# ATMEGA16.net
KiCad netlist of a schematic drawn in Altium Designer
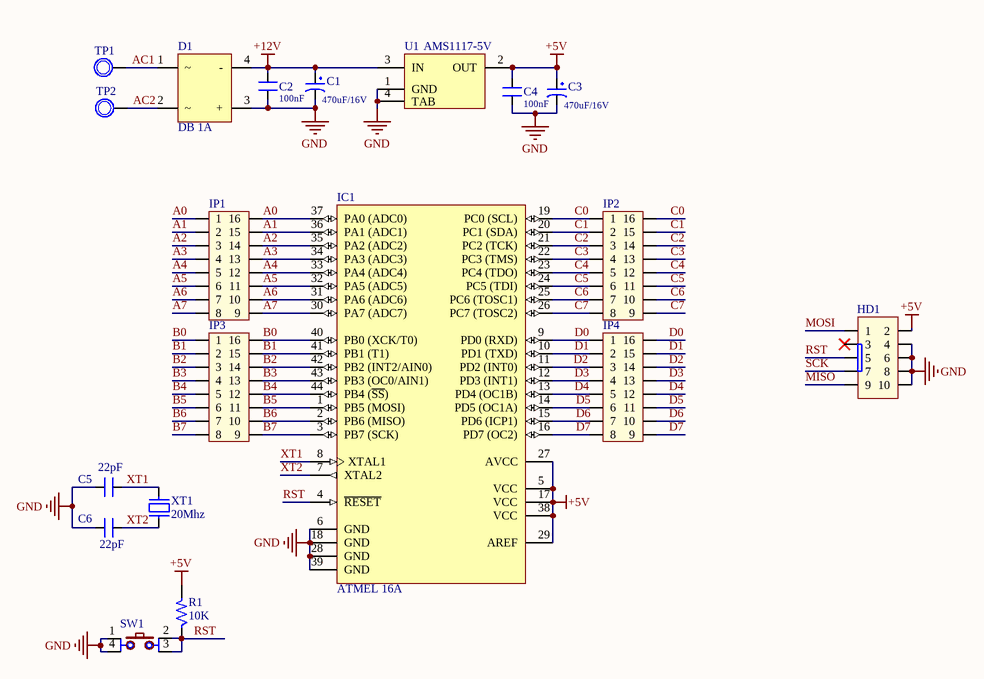
[diagram p0: ATMEGA16.SchDoc]

(export (version "E")
  (design (tool "Eeschema 10.0.6"))
  (components
    (comp (ref "C1")
      (value "470uF/16V")
      (footprint "C-TANT-7343")
      (libsource (lib "MrQuan") (part "Capacitor"))
    )
    (comp (ref "C2") (value "100nF") (footprint "CER-0805") (libsource (lib "MrQuan") (part "Ceramic")))
    (comp (ref "C3")
      (value "470uF/16V")
      (footprint "C-TANT-7343")
      (libsource (lib "MrQuan") (part "Capacitor"))
    )
    (comp (ref "C4") (value "100nF") (footprint "CER-0805") (libsource (lib "MrQuan") (part "Ceramic")))
    (comp (ref "C5") (value "22pF") (footprint "CER-0805") (libsource (lib "MrQuan") (part "Ceramic")))
    (comp (ref "C6") (value "22pF") (footprint "CER-0805") (libsource (lib "MrQuan") (part "Ceramic")))
    (comp (ref "D1")
      (value "DB 1A")
      (footprint "D-DB-1A-SMD")
      (libsource (lib "doAnTotNghiep2017Lib") (part "DB"))
    )
    (comp (ref "HD1") (value "Header 5x2") (footprint "Hed2X5") (libsource (lib "PART") (part "HED5x2_S")))
    (comp (ref "IC1")
      (value "ATMEL 16A")
      (footprint "TQFP44")
      (libsource (lib "LIBRARY") (part "ATmega16A-AU"))
    )
    (comp (ref "IP1") (value "JP8X2") (footprint "JP8X2") (libsource (lib "syhaunguyen") (part "JP8X2")))
    (comp (ref "IP2") (value "JP8X2") (footprint "JP8X2") (libsource (lib "syhaunguyen") (part "JP8X2")))
    (comp (ref "IP3") (value "JP8X2") (footprint "JP8X2") (libsource (lib "syhaunguyen") (part "JP8X2")))
    (comp (ref "IP4") (value "JP8X2") (footprint "JP8X2") (libsource (lib "syhaunguyen") (part "JP8X2")))
    (comp (ref "R1") (value "10K") (footprint "RES-0805") (libsource (lib "MrQuan") (part "Res1/4W")))
    (comp (ref "SW1")
      (value "SW")
      (footprint "SW2-SMD")
      (description "Switch button 4 pin")
      (libsource (lib "LIBRARY") (part "SW4"))
    )
    (comp (ref "TP1") (value "TP") (footprint "MrQuan:TP") (libsource (lib "MrQuan") (part "TP")))
    (comp (ref "TP2") (value "TP") (footprint "MrQuan:TP") (libsource (lib "MrQuan") (part "TP")))
    (comp (ref "U1")
      (value "AMS1117-5V")
      (footprint "LM1117")
      (description "800mA Low-Dropout Linear Regulator")
      (fields
        (field (name "PARTNUMBER") "LM1117IMP-3.3")
        (field (name "MANUFACTURER") "National Semiconductor")
        (field (name "PUBLISHER") "Altium Limited")
      )
      (libsource (lib "VNSKILLS2014-ASM") (part "LM1117IMP-3.3"))
    )
    (comp (ref "XT1")
      (value "20Mhz")
      (footprint "XTAL-RU49/4")
      (description "Crystal, 32.768 KHz, -40 to 85 degC, 3.2 x 1.5 x 0.9 mm SMD")
      (libsource (lib "LIBRARY") (part "XT2"))
    )
  )
  (nets
    (net (code "1") (name "+5V") (class "Default")
      (node (ref "C3") (pin "1") (pinfunction "1_1") (pintype "passive"))
      (node (ref "C4") (pin "2") (pinfunction "2_2") (pintype "passive"))
      (node (ref "HD1") (pin "2") (pinfunction "2_2") (pintype "passive"))
      (node (ref "IC1") (pin "17") (pinfunction "VCC_17") (pintype "power_in"))
      (node (ref "IC1") (pin "27") (pinfunction "AVCC_27") (pintype "power_in"))
      (node (ref "IC1") (pin "29") (pinfunction "AREF_29") (pintype "power_in"))
      (node (ref "IC1") (pin "38") (pinfunction "VCC_38") (pintype "power_in"))
      (node (ref "IC1") (pin "5") (pinfunction "VCC_5") (pintype "power_in"))
      (node (ref "R1") (pin "2") (pinfunction "2_2") (pintype "passive"))
      (node (ref "U1") (pin "2") (pinfunction "OUT_2") (pintype "power_in"))
    )
    (net (code "2") (name "+12V") (class "Default")
      (node (ref "C1") (pin "1") (pinfunction "1_1") (pintype "passive"))
      (node (ref "C2") (pin "2") (pinfunction "2_2") (pintype "passive"))
      (node (ref "D1") (pin "4") (pinfunction "-_4") (pintype "passive"))
      (node (ref "U1") (pin "3") (pinfunction "IN_3") (pintype "power_in"))
    )
    (net (code "3") (name "/A0") (class "Default")
      (node (ref "IC1") (pin "37") (pinfunction "PA0_(ADC0)_37") (pintype "bidirectional"))
      (node (ref "IP1") (pin "1") (pinfunction "1_1") (pintype "passive"))
      (node (ref "IP1") (pin "16") (pinfunction "16_16") (pintype "passive"))
    )
    (net (code "4") (name "/A1") (class "Default")
      (node (ref "IC1") (pin "36") (pinfunction "PA1_(ADC1)_36") (pintype "bidirectional"))
      (node (ref "IP1") (pin "15") (pinfunction "15_15") (pintype "passive"))
      (node (ref "IP1") (pin "2") (pinfunction "2_2") (pintype "passive"))
    )
    (net (code "5") (name "/A2") (class "Default")
      (node (ref "IC1") (pin "35") (pinfunction "PA2_(ADC2)_35") (pintype "bidirectional"))
      (node (ref "IP1") (pin "14") (pinfunction "14_14") (pintype "passive"))
      (node (ref "IP1") (pin "3") (pinfunction "3_3") (pintype "passive"))
    )
    (net (code "6") (name "/A3") (class "Default")
      (node (ref "IC1") (pin "34") (pinfunction "PA3_(ADC3)_34") (pintype "bidirectional"))
      (node (ref "IP1") (pin "13") (pinfunction "13_13") (pintype "passive"))
      (node (ref "IP1") (pin "4") (pinfunction "4_4") (pintype "passive"))
    )
    (net (code "7") (name "/A4") (class "Default")
      (node (ref "IC1") (pin "33") (pinfunction "PA4_(ADC4)_33") (pintype "bidirectional"))
      (node (ref "IP1") (pin "12") (pinfunction "12_12") (pintype "passive"))
      (node (ref "IP1") (pin "5") (pinfunction "5_5") (pintype "passive"))
    )
    (net (code "8") (name "/A5") (class "Default")
      (node (ref "IC1") (pin "32") (pinfunction "PA5_(ADC5)_32") (pintype "bidirectional"))
      (node (ref "IP1") (pin "11") (pinfunction "11_11") (pintype "passive"))
      (node (ref "IP1") (pin "6") (pinfunction "6_6") (pintype "passive"))
    )
    (net (code "9") (name "/A6") (class "Default")
      (node (ref "IC1") (pin "31") (pinfunction "PA6_(ADC6)_31") (pintype "bidirectional"))
      (node (ref "IP1") (pin "10") (pinfunction "10_10") (pintype "passive"))
      (node (ref "IP1") (pin "7") (pinfunction "7_7") (pintype "passive"))
    )
    (net (code "10") (name "/A7") (class "Default")
      (node (ref "IC1") (pin "30") (pinfunction "PA7_(ADC7)_30") (pintype "bidirectional"))
      (node (ref "IP1") (pin "8") (pinfunction "8_8") (pintype "passive"))
      (node (ref "IP1") (pin "9") (pinfunction "9_9") (pintype "passive"))
    )
    (net (code "11") (name "/AC1") (class "Default")
      (node (ref "D1") (pin "1") (pinfunction "~_1") (pintype "passive"))
      (node (ref "TP1") (pin "1") (pintype "passive"))
    )
    (net (code "12") (name "/AC2") (class "Default")
      (node (ref "D1") (pin "2") (pinfunction "~_2") (pintype "passive"))
      (node (ref "TP2") (pin "1") (pintype "passive"))
    )
    (net (code "13") (name "/B0") (class "Default")
      (node (ref "IC1") (pin "40") (pinfunction "PB0_(XCK/T0)_40") (pintype "bidirectional"))
      (node (ref "IP3") (pin "1") (pinfunction "1_1") (pintype "passive"))
      (node (ref "IP3") (pin "16") (pinfunction "16_16") (pintype "passive"))
    )
    (net (code "14") (name "/B1") (class "Default")
      (node (ref "IC1") (pin "41") (pinfunction "PB1_(T1)_41") (pintype "bidirectional"))
      (node (ref "IP3") (pin "15") (pinfunction "15_15") (pintype "passive"))
      (node (ref "IP3") (pin "2") (pinfunction "2_2") (pintype "passive"))
    )
    (net (code "15") (name "/B2") (class "Default")
      (node (ref "IC1") (pin "42") (pinfunction "PB2_(INT2/AIN0)_42") (pintype "bidirectional"))
      (node (ref "IP3") (pin "14") (pinfunction "14_14") (pintype "passive"))
      (node (ref "IP3") (pin "3") (pinfunction "3_3") (pintype "passive"))
    )
    (net (code "16") (name "/B3") (class "Default")
      (node (ref "IC1") (pin "43") (pinfunction "PB3_(OC0/AIN1)_43") (pintype "bidirectional"))
      (node (ref "IP3") (pin "13") (pinfunction "13_13") (pintype "passive"))
      (node (ref "IP3") (pin "4") (pinfunction "4_4") (pintype "passive"))
    )
    (net (code "17") (name "/B4") (class "Default")
      (node (ref "IC1") (pin "44") (pinfunction "PB4_(~{SS})_44") (pintype "bidirectional"))
      (node (ref "IP3") (pin "12") (pinfunction "12_12") (pintype "passive"))
      (node (ref "IP3") (pin "5") (pinfunction "5_5") (pintype "passive"))
    )
    (net (code "18") (name "/B5") (class "Default")
      (node (ref "IC1") (pin "1") (pinfunction "PB5_(MOSI)_1") (pintype "bidirectional"))
      (node (ref "IP3") (pin "11") (pinfunction "11_11") (pintype "passive"))
      (node (ref "IP3") (pin "6") (pinfunction "6_6") (pintype "passive"))
    )
    (net (code "19") (name "/B6") (class "Default")
      (node (ref "IC1") (pin "2") (pinfunction "PB6_(MISO)_2") (pintype "bidirectional"))
      (node (ref "IP3") (pin "10") (pinfunction "10_10") (pintype "passive"))
      (node (ref "IP3") (pin "7") (pinfunction "7_7") (pintype "passive"))
    )
    (net (code "20") (name "/B7") (class "Default")
      (node (ref "IC1") (pin "3") (pinfunction "PB7_(SCK)_3") (pintype "bidirectional"))
      (node (ref "IP3") (pin "8") (pinfunction "8_8") (pintype "passive"))
      (node (ref "IP3") (pin "9") (pinfunction "9_9") (pintype "passive"))
    )
    (net (code "21") (name "/C0") (class "Default")
      (node (ref "IC1") (pin "19") (pinfunction "PC0_(SCL)_19") (pintype "bidirectional"))
      (node (ref "IP2") (pin "1") (pinfunction "1_1") (pintype "passive"))
      (node (ref "IP2") (pin "16") (pinfunction "16_16") (pintype "passive"))
    )
    (net (code "22") (name "/C1") (class "Default")
      (node (ref "IC1") (pin "20") (pinfunction "PC1_(SDA)_20") (pintype "bidirectional"))
      (node (ref "IP2") (pin "15") (pinfunction "15_15") (pintype "passive"))
      (node (ref "IP2") (pin "2") (pinfunction "2_2") (pintype "passive"))
    )
    (net (code "23") (name "/C2") (class "Default")
      (node (ref "IC1") (pin "21") (pinfunction "PC2_(TCK)_21") (pintype "bidirectional"))
      (node (ref "IP2") (pin "14") (pinfunction "14_14") (pintype "passive"))
      (node (ref "IP2") (pin "3") (pinfunction "3_3") (pintype "passive"))
    )
    (net (code "24") (name "/C3") (class "Default")
      (node (ref "IC1") (pin "22") (pinfunction "PC3_(TMS)_22") (pintype "bidirectional"))
      (node (ref "IP2") (pin "13") (pinfunction "13_13") (pintype "passive"))
      (node (ref "IP2") (pin "4") (pinfunction "4_4") (pintype "passive"))
    )
    (net (code "25") (name "/C4") (class "Default")
      (node (ref "IC1") (pin "23") (pinfunction "PC4_(TDO)_23") (pintype "bidirectional"))
      (node (ref "IP2") (pin "12") (pinfunction "12_12") (pintype "passive"))
      (node (ref "IP2") (pin "5") (pinfunction "5_5") (pintype "passive"))
    )
    (net (code "26") (name "/C5") (class "Default")
      (node (ref "IC1") (pin "24") (pinfunction "PC5_(TDI)_24") (pintype "bidirectional"))
      (node (ref "IP2") (pin "11") (pinfunction "11_11") (pintype "passive"))
      (node (ref "IP2") (pin "6") (pinfunction "6_6") (pintype "passive"))
    )
    (net (code "27") (name "/C6") (class "Default")
      (node (ref "IC1") (pin "25") (pinfunction "PC6_(TOSC1)_25") (pintype "bidirectional"))
      (node (ref "IP2") (pin "10") (pinfunction "10_10") (pintype "passive"))
      (node (ref "IP2") (pin "7") (pinfunction "7_7") (pintype "passive"))
    )
    (net (code "28") (name "/C7") (class "Default")
      (node (ref "IC1") (pin "26") (pinfunction "PC7_(TOSC2)_26") (pintype "bidirectional"))
      (node (ref "IP2") (pin "8") (pinfunction "8_8") (pintype "passive"))
      (node (ref "IP2") (pin "9") (pinfunction "9_9") (pintype "passive"))
    )
    (net (code "29") (name "/D0") (class "Default")
      (node (ref "IC1") (pin "9") (pinfunction "PD0_(RXD)_9") (pintype "bidirectional"))
      (node (ref "IP4") (pin "1") (pinfunction "1_1") (pintype "passive"))
      (node (ref "IP4") (pin "16") (pinfunction "16_16") (pintype "passive"))
    )
    (net (code "30") (name "/D1") (class "Default")
      (node (ref "IC1") (pin "10") (pinfunction "PD1_(TXD)_10") (pintype "bidirectional"))
      (node (ref "IP4") (pin "15") (pinfunction "15_15") (pintype "passive"))
      (node (ref "IP4") (pin "2") (pinfunction "2_2") (pintype "passive"))
    )
    (net (code "31") (name "/D2") (class "Default")
      (node (ref "IC1") (pin "11") (pinfunction "PD2_(INT0)_11") (pintype "bidirectional"))
      (node (ref "IP4") (pin "14") (pinfunction "14_14") (pintype "passive"))
      (node (ref "IP4") (pin "3") (pinfunction "3_3") (pintype "passive"))
    )
    (net (code "32") (name "/D3") (class "Default")
      (node (ref "IC1") (pin "12") (pinfunction "PD3_(INT1)_12") (pintype "bidirectional"))
      (node (ref "IP4") (pin "13") (pinfunction "13_13") (pintype "passive"))
      (node (ref "IP4") (pin "4") (pinfunction "4_4") (pintype "passive"))
    )
    (net (code "33") (name "/D4") (class "Default")
      (node (ref "IC1") (pin "13") (pinfunction "PD4_(OC1B)_13") (pintype "bidirectional"))
      (node (ref "IP4") (pin "12") (pinfunction "12_12") (pintype "passive"))
      (node (ref "IP4") (pin "5") (pinfunction "5_5") (pintype "passive"))
    )
    (net (code "34") (name "/D5") (class "Default")
      (node (ref "IC1") (pin "14") (pinfunction "PD5_(OC1A)_14") (pintype "bidirectional"))
      (node (ref "IP4") (pin "11") (pinfunction "11_11") (pintype "passive"))
      (node (ref "IP4") (pin "6") (pinfunction "6_6") (pintype "passive"))
    )
    (net (code "35") (name "/D6") (class "Default")
      (node (ref "IC1") (pin "15") (pinfunction "PD6_(ICP1)_15") (pintype "bidirectional"))
      (node (ref "IP4") (pin "10") (pinfunction "10_10") (pintype "passive"))
      (node (ref "IP4") (pin "7") (pinfunction "7_7") (pintype "passive"))
    )
    (net (code "36") (name "/D7") (class "Default")
      (node (ref "IC1") (pin "16") (pinfunction "PD7_(OC2)_16") (pintype "bidirectional"))
      (node (ref "IP4") (pin "8") (pinfunction "8_8") (pintype "passive"))
      (node (ref "IP4") (pin "9") (pinfunction "9_9") (pintype "passive"))
    )
    (net (code "37") (name "/MISO") (class "Default")
      (node (ref "HD1") (pin "9") (pinfunction "9_9") (pintype "passive"))
    )
    (net (code "38") (name "/MOSI") (class "Default")
      (node (ref "HD1") (pin "1") (pinfunction "1_1") (pintype "passive"))
    )
    (net (code "39") (name "/RST") (class "Default")
      (node (ref "HD1") (pin "5") (pinfunction "5_5") (pintype "passive"))
      (node (ref "IC1") (pin "4") (pinfunction "~{RESET}_4") (pintype "input"))
      (node (ref "R1") (pin "1") (pinfunction "1_1") (pintype "passive"))
      (node (ref "SW1") (pin "2") (pinfunction "2_2") (pintype "passive"))
      (node (ref "SW1") (pin "3") (pinfunction "3_3") (pintype "passive"))
    )
    (net (code "40") (name "/SCK") (class "Default")
      (node (ref "HD1") (pin "7") (pinfunction "7_7") (pintype "passive"))
    )
    (net (code "41") (name "/XT1") (class "Default")
      (node (ref "C5") (pin "2") (pinfunction "2_2") (pintype "passive"))
      (node (ref "IC1") (pin "8") (pinfunction "XTAL1_8") (pintype "input"))
      (node (ref "XT1") (pin "2") (pinfunction "2_2") (pintype "passive"))
    )
    (net (code "42") (name "/XT2") (class "Default")
      (node (ref "C6") (pin "2") (pinfunction "2_2") (pintype "passive"))
      (node (ref "IC1") (pin "7") (pinfunction "XTAL2_7") (pintype "output"))
      (node (ref "XT1") (pin "1") (pinfunction "1_1") (pintype "passive"))
    )
    (net (code "43") (name "GND") (class "Default")
      (node (ref "C1") (pin "2") (pinfunction "2_2") (pintype "passive"))
      (node (ref "C2") (pin "1") (pinfunction "1_1") (pintype "passive"))
      (node (ref "C3") (pin "2") (pinfunction "2_2") (pintype "passive"))
      (node (ref "C4") (pin "1") (pinfunction "1_1") (pintype "passive"))
      (node (ref "C5") (pin "1") (pinfunction "1_1") (pintype "passive"))
      (node (ref "C6") (pin "1") (pinfunction "1_1") (pintype "passive"))
      (node (ref "D1") (pin "3") (pinfunction "+_3") (pintype "passive"))
      (node (ref "HD1") (pin "10") (pinfunction "10_10") (pintype "passive"))
      (node (ref "HD1") (pin "4") (pinfunction "4_4") (pintype "passive"))
      (node (ref "HD1") (pin "6") (pinfunction "6_6") (pintype "passive"))
      (node (ref "HD1") (pin "8") (pinfunction "8_8") (pintype "passive"))
      (node (ref "IC1") (pin "18") (pinfunction "GND_18") (pintype "power_in"))
      (node (ref "IC1") (pin "28") (pinfunction "GND_28") (pintype "power_in"))
      (node (ref "IC1") (pin "39") (pinfunction "GND_39") (pintype "power_in"))
      (node (ref "IC1") (pin "6") (pinfunction "GND_6") (pintype "power_in"))
      (node (ref "SW1") (pin "1") (pintype "passive"))
      (node (ref "SW1") (pin "4") (pinfunction "4_4") (pintype "passive"))
      (node (ref "U1") (pin "1") (pinfunction "GND_1") (pintype "power_in"))
      (node (ref "U1") (pin "4") (pinfunction "TAB_4") (pintype "power_in"))
    )
    (net (code "44") (name "unconnected-(HD1-Pad3)") (class "Default")
      (node (ref "HD1") (pin "3") (pinfunction "3_3") (pintype "passive+no_connect"))
    )
  )
)
